# MicroMySens-v003.net
KiCad netlist of a schematic drawn in EAGLE
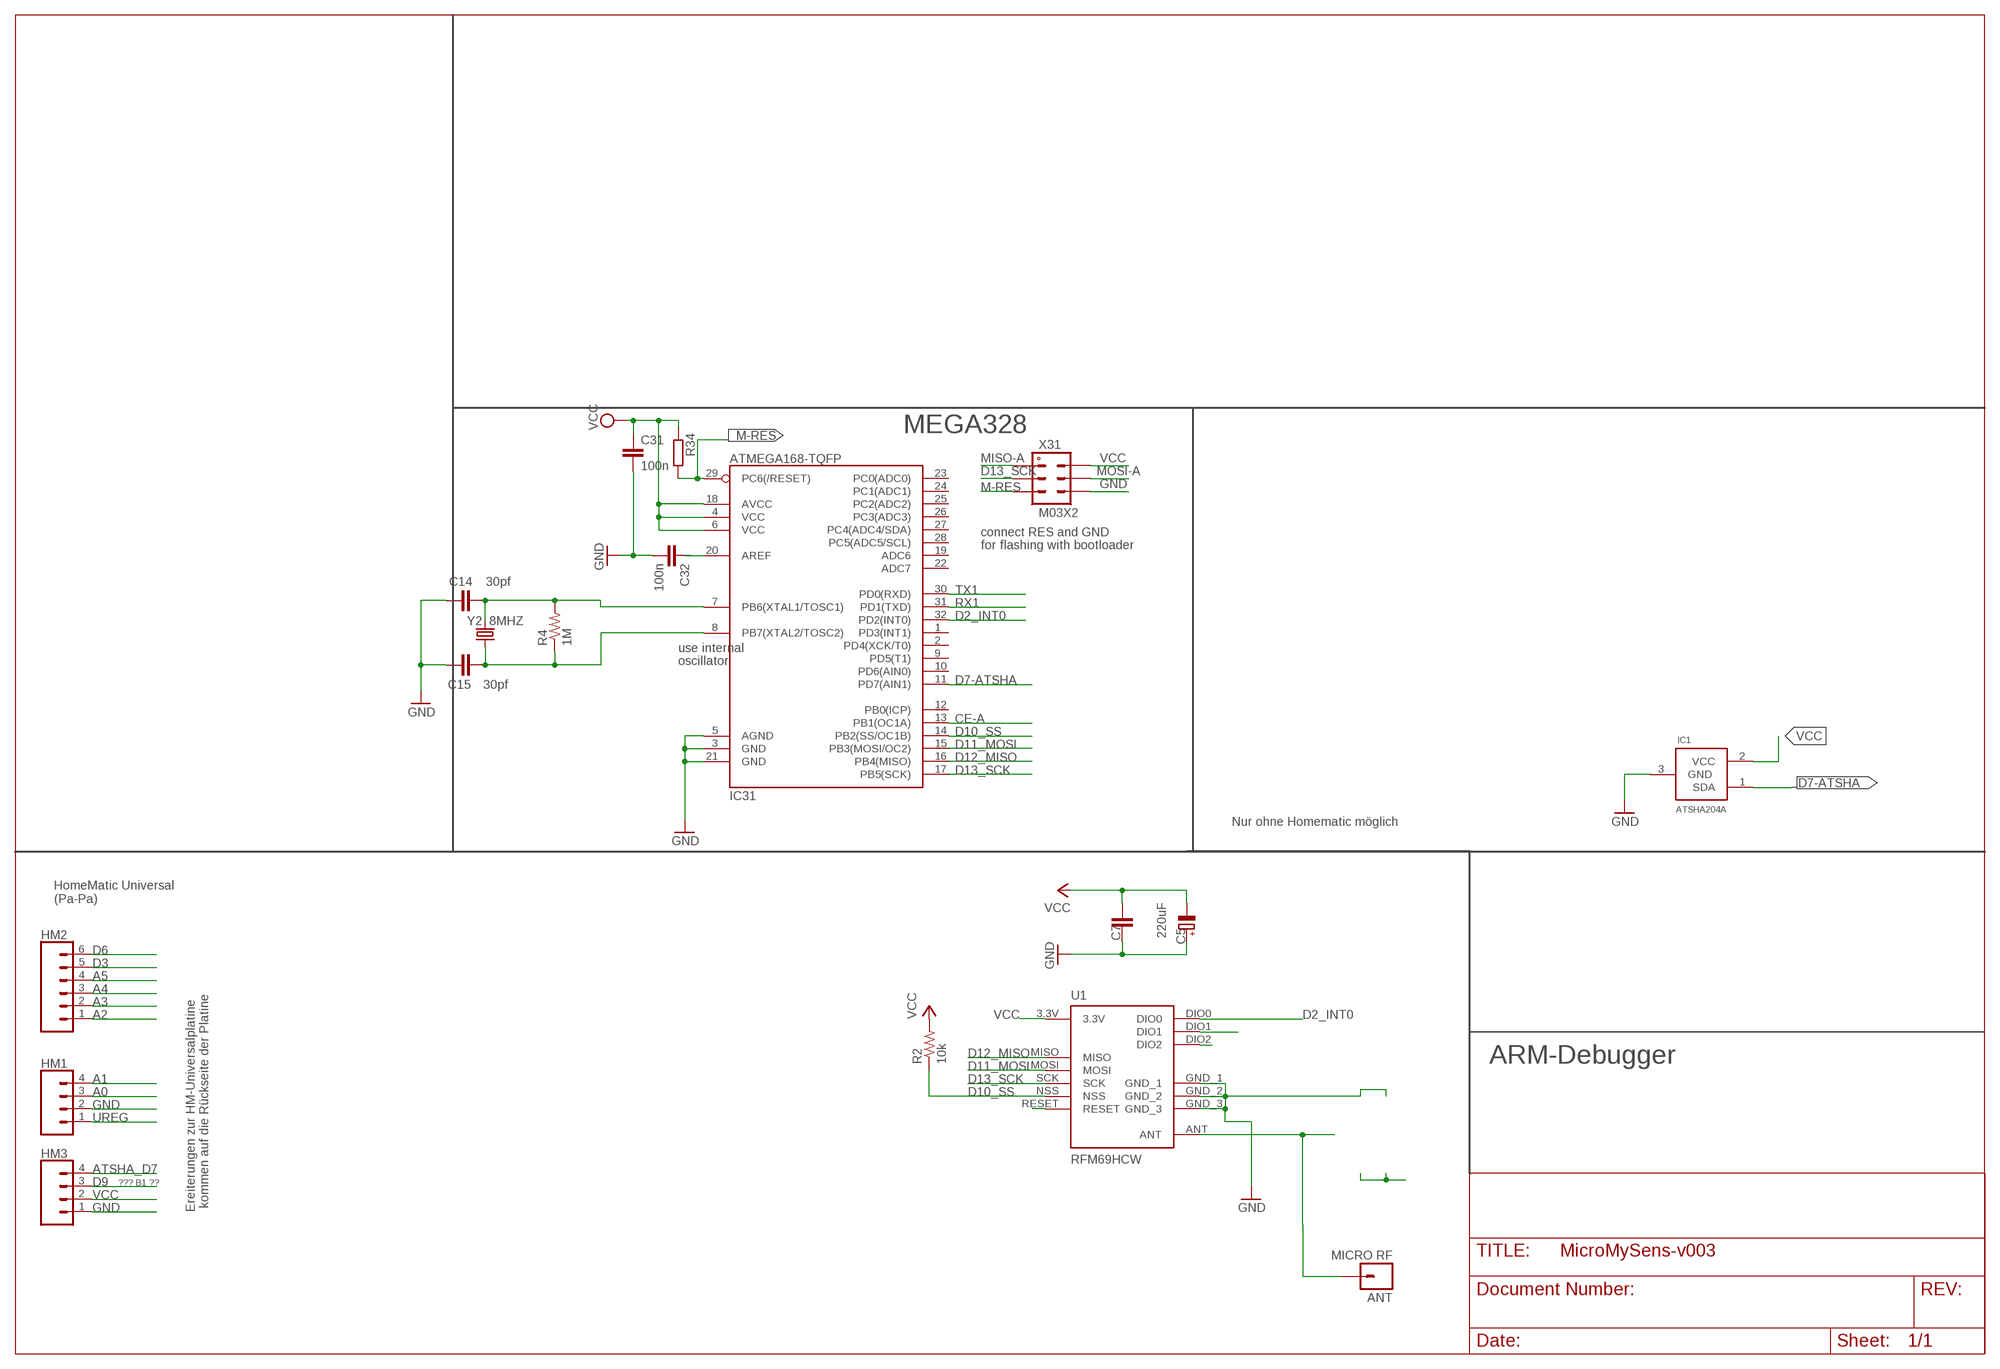
[diagram p0: schematic, sheet 1]

(export (version "E")
  (design (tool "Eeschema 10.0.6"))
  (components
    (comp (ref "ANT")
      (value "MICRO RF")
      (footprint "eagle-import:1X01")
      (libsource (lib "eagle-import") (part "M01PTH"))
    )
    (comp (ref "C5")
      (value "220uF")
      (footprint "eagle-import:E5-8,5")
      (libsource (lib "eagle-import") (part "CPOL-EUE5-8.5"))
    )
    (comp (ref "C7")
      (value "C-EUC1812")
      (footprint "eagle-import:C1812")
      (libsource (lib "eagle-import") (part "C-EUC1812"))
    )
    (comp (ref "C14")
      (value "30pf")
      (footprint "eagle-import:0805")
      (libsource (lib "eagle-import") (part "CAP0805"))
    )
    (comp (ref "C15")
      (value "30pf")
      (footprint "eagle-import:0805")
      (libsource (lib "eagle-import") (part "CAP0805"))
    )
    (comp (ref "C31")
      (value "100n")
      (footprint "eagle-import:C0805")
      (libsource (lib "eagle-import") (part "C-EUC0805"))
    )
    (comp (ref "C32")
      (value "100n")
      (footprint "eagle-import:C0805")
      (libsource (lib "eagle-import") (part "C-EUC0805"))
    )
    (comp (ref "HM1")
      (value "CONN_04")
      (footprint "eagle-import:1X04")
      (libsource (lib "eagle-import") (part "CONN_04"))
    )
    (comp (ref "HM2")
      (value "CONN_06SILK_FEMALE_PTH")
      (footprint "eagle-import:1X06")
      (libsource (lib "eagle-import") (part "CONN_06SILK_FEMALE_PTH"))
    )
    (comp (ref "HM3")
      (value "CONN_04")
      (footprint "eagle-import:1X04")
      (libsource (lib "eagle-import") (part "CONN_04"))
    )
    (comp (ref "IC1")
      (value "ATSHA204A")
      (footprint "eagle-import:SOT23")
      (libsource (lib "eagle-import") (part "ATSHA204A"))
    )
    (comp (ref "IC31")
      (value "ATMEGA168-TQFP")
      (footprint "eagle-import:TQFP32-08")
      (libsource (lib "eagle-import") (part "ATMEGA168-TQFP"))
    )
    (comp (ref "R2")
      (value "10k")
      (footprint "eagle-import:0805")
      (libsource (lib "eagle-import") (part "RESISTOR0805-RES"))
    )
    (comp (ref "R4")
      (value "1M")
      (footprint "eagle-import:0805")
      (libsource (lib "eagle-import") (part "RESISTOR0805-RES"))
    )
    (comp (ref "R34")
      (value "R-EU_R0805")
      (footprint "eagle-import:R0805")
      (libsource (lib "eagle-import") (part "R-EU_R0805"))
    )
    (comp (ref "U1")
      (value "RFM69HCW")
      (footprint "eagle-import:RFM69HCW-XXXS2")
      (libsource (lib "eagle-import") (part "RFM69HCW"))
    )
    (comp (ref "X31")
      (value "M03X2")
      (footprint "eagle-import:2X03-1.27MM_SMD")
      (libsource (lib "eagle-import") (part "M03X2"))
    )
    (comp (ref "Y2")
      (value "8MHZ")
      (footprint "eagle-import:CRYSTAL-TXC-7A")
      (libsource (lib "eagle-import") (part "CRYSTALTXC-7A"))
    )
  )
  (nets
    (net (code "1") (name "/A0") (class "Default")
      (node (ref "HM1") (pin "3") (pinfunction "3_3") (pintype "passive"))
    )
    (net (code "2") (name "/A1") (class "Default")
      (node (ref "HM1") (pin "4") (pinfunction "4_4") (pintype "passive"))
    )
    (net (code "3") (name "/A2") (class "Default")
      (node (ref "HM2") (pin "1") (pinfunction "1_1") (pintype "passive"))
    )
    (net (code "4") (name "/A3") (class "Default")
      (node (ref "HM2") (pin "2") (pinfunction "2_2") (pintype "passive"))
    )
    (net (code "5") (name "/A4") (class "Default")
      (node (ref "HM2") (pin "3") (pinfunction "3_3") (pintype "passive"))
    )
    (net (code "6") (name "/A5") (class "Default")
      (node (ref "HM2") (pin "4") (pinfunction "4_4") (pintype "passive"))
    )
    (net (code "7") (name "/ATSHA_D7") (class "Default")
      (node (ref "HM3") (pin "4") (pinfunction "4_4") (pintype "passive"))
    )
    (net (code "8") (name "/CE-A") (class "Default")
      (node (ref "IC31") (pin "13") (pinfunction "PB1(OC1A)_13") (pintype "bidirectional"))
    )
    (net (code "9") (name "/D2_INT0") (class "Default")
      (node (ref "IC31") (pin "32") (pinfunction "PD2(INT0)_32") (pintype "bidirectional"))
      (node (ref "U1") (pin "DIO0") (pinfunction "DIO0_DIO0") (pintype "bidirectional"))
    )
    (net (code "10") (name "/D3") (class "Default")
      (node (ref "HM2") (pin "5") (pinfunction "5_5") (pintype "passive"))
    )
    (net (code "11") (name "/D6") (class "Default")
      (node (ref "HM2") (pin "6") (pinfunction "6_6") (pintype "passive"))
    )
    (net (code "12") (name "/D7-ATSHA") (class "Default")
      (node (ref "IC1") (pin "1") (pinfunction "SDA_1") (pintype "bidirectional"))
      (node (ref "IC31") (pin "11") (pinfunction "PD7(AIN1)_11") (pintype "bidirectional"))
    )
    (net (code "13") (name "/D9") (class "Default")
      (node (ref "HM3") (pin "3") (pinfunction "3_3") (pintype "passive"))
    )
    (net (code "14") (name "/D10_SS") (class "Default")
      (node (ref "IC31") (pin "14") (pinfunction "PB2(SS/OC1B)_14") (pintype "bidirectional"))
      (node (ref "R2") (pin "1") (pinfunction "1_1") (pintype "passive"))
      (node (ref "U1") (pin "NSS") (pinfunction "NSS_NSS") (pintype "input"))
    )
    (net (code "15") (name "/D11_MOSI") (class "Default")
      (node (ref "IC31") (pin "15") (pinfunction "PB3(MOSI/OC2)_15") (pintype "bidirectional"))
      (node (ref "U1") (pin "MOSI") (pinfunction "MOSI_MOSI") (pintype "input"))
    )
    (net (code "16") (name "/D12_MISO") (class "Default")
      (node (ref "IC31") (pin "16") (pinfunction "PB4(MISO)_16") (pintype "bidirectional"))
      (node (ref "U1") (pin "MISO") (pinfunction "MISO_MISO") (pintype "bidirectional"))
    )
    (net (code "17") (name "/D13_SCK") (class "Default")
      (node (ref "IC31") (pin "17") (pinfunction "PB5(SCK)_17") (pintype "bidirectional"))
      (node (ref "U1") (pin "SCK") (pinfunction "SCK_SCK") (pintype "input"))
      (node (ref "X31") (pin "P$3") (pinfunction "3_P$3") (pintype "passive"))
    )
    (net (code "18") (name "/M-RES") (class "Default")
      (node (ref "IC31") (pin "29") (pinfunction "PC6(/RESET)_29") (pintype "bidirectional"))
      (node (ref "R34") (pin "2") (pinfunction "2_2") (pintype "passive"))
      (node (ref "X31") (pin "P$5") (pinfunction "5_P$5") (pintype "passive"))
    )
    (net (code "19") (name "/MISO-A") (class "Default")
      (node (ref "X31") (pin "P$1") (pinfunction "1_P$1") (pintype "passive"))
    )
    (net (code "20") (name "/MOSI-A") (class "Default")
      (node (ref "X31") (pin "P$4") (pinfunction "4_P$4") (pintype "passive"))
    )
    (net (code "21") (name "/RX1") (class "Default")
      (node (ref "IC31") (pin "31") (pinfunction "PD1(TXD)_31") (pintype "bidirectional"))
    )
    (net (code "22") (name "/TX1") (class "Default")
      (node (ref "IC31") (pin "30") (pinfunction "PD0(RXD)_30") (pintype "bidirectional"))
    )
    (net (code "23") (name "/UREG") (class "Default")
      (node (ref "HM1") (pin "1") (pinfunction "1_1") (pintype "passive"))
    )
    (net (code "24") (name "GND") (class "Default")
      (node (ref "C14") (pin "1") (pinfunction "1_1") (pintype "passive"))
      (node (ref "C15") (pin "1") (pinfunction "1_1") (pintype "passive"))
      (node (ref "C31") (pin "2") (pinfunction "2_2") (pintype "passive"))
      (node (ref "C32") (pin "2") (pinfunction "2_2") (pintype "passive"))
      (node (ref "C5") (pin "+") (pinfunction "+_+") (pintype "passive"))
      (node (ref "C7") (pin "2") (pinfunction "2_2") (pintype "passive"))
      (node (ref "HM1") (pin "2") (pinfunction "2_2") (pintype "passive"))
      (node (ref "HM3") (pin "1") (pinfunction "1_1") (pintype "passive"))
      (node (ref "IC1") (pin "3") (pinfunction "GND_3") (pintype "bidirectional"))
      (node (ref "IC31") (pin "21") (pinfunction "GND_21") (pintype "bidirectional"))
      (node (ref "IC31") (pin "3") (pinfunction "GND_3") (pintype "bidirectional"))
      (node (ref "IC31") (pin "5") (pinfunction "AGND_5") (pintype "bidirectional"))
      (node (ref "U1") (pin "GND_1") (pinfunction "GND_1_GND_1") (pintype "power_in"))
      (node (ref "U1") (pin "GND_2") (pinfunction "GND_2_GND_2") (pintype "power_in"))
      (node (ref "U1") (pin "GND_3") (pinfunction "GND_3_GND_3") (pintype "power_in"))
      (node (ref "X31") (pin "P$6") (pinfunction "6_P$6") (pintype "passive"))
    )
    (net (code "25") (name "Net-(ANT-Pad1)") (class "Default")
      (node (ref "ANT") (pin "1") (pinfunction "1_1") (pintype "passive"))
      (node (ref "U1") (pin "ANT") (pinfunction "ANT_ANT") (pintype "passive"))
    )
    (net (code "26") (name "Net-(IC31-AREF)") (class "Default")
      (node (ref "C32") (pin "1") (pinfunction "1_1") (pintype "passive"))
      (node (ref "IC31") (pin "20") (pinfunction "AREF_20") (pintype "bidirectional"))
    )
    (net (code "27") (name "Net-(IC31-PB6(XTAL1{slash}TOSC1))") (class "Default")
      (node (ref "C14") (pin "2") (pinfunction "2_2") (pintype "passive"))
      (node (ref "IC31") (pin "7") (pinfunction "PB6(XTAL1/TOSC1)_7") (pintype "bidirectional"))
      (node (ref "R4") (pin "2") (pinfunction "2_2") (pintype "passive"))
      (node (ref "Y2") (pin "P$2") (pinfunction "2_P$2") (pintype "passive"))
    )
    (net (code "28") (name "Net-(IC31-PB7(XTAL2{slash}TOSC2))") (class "Default")
      (node (ref "C15") (pin "2") (pinfunction "2_2") (pintype "passive"))
      (node (ref "IC31") (pin "8") (pinfunction "PB7(XTAL2/TOSC2)_8") (pintype "bidirectional"))
      (node (ref "R4") (pin "1") (pinfunction "1_1") (pintype "passive"))
      (node (ref "Y2") (pin "P$1") (pinfunction "1_P$1") (pintype "passive"))
    )
    (net (code "29") (name "VCC") (class "Default")
      (node (ref "C31") (pin "1") (pinfunction "1_1") (pintype "passive"))
      (node (ref "C5") (pin "-") (pinfunction "-_-") (pintype "passive"))
      (node (ref "C7") (pin "1") (pinfunction "1_1") (pintype "passive"))
      (node (ref "HM3") (pin "2") (pinfunction "2_2") (pintype "passive"))
      (node (ref "IC1") (pin "2") (pinfunction "VCC_2") (pintype "bidirectional"))
      (node (ref "IC31") (pin "18") (pinfunction "AVCC_18") (pintype "bidirectional"))
      (node (ref "IC31") (pin "4") (pinfunction "VCC_4") (pintype "bidirectional"))
      (node (ref "IC31") (pin "6") (pinfunction "VCC_6") (pintype "bidirectional"))
      (node (ref "R2") (pin "2") (pinfunction "2_2") (pintype "passive"))
      (node (ref "R34") (pin "1") (pinfunction "1_1") (pintype "passive"))
      (node (ref "U1") (pin "3.3V") (pinfunction "3.3V_3.3V") (pintype "power_in"))
      (node (ref "X31") (pin "P$2") (pinfunction "2_P$2") (pintype "passive"))
    )
    (net (code "30") (name "unconnected-(IC31-ADC6-Pad19)") (class "Default")
      (node (ref "IC31") (pin "19") (pinfunction "ADC6_19") (pintype "bidirectional"))
    )
    (net (code "31") (name "unconnected-(IC31-ADC7-Pad22)") (class "Default")
      (node (ref "IC31") (pin "22") (pinfunction "ADC7_22") (pintype "bidirectional"))
    )
    (net (code "32") (name "unconnected-(IC31-PB0(ICP)-Pad12)") (class "Default")
      (node (ref "IC31") (pin "12") (pinfunction "PB0(ICP)_12") (pintype "bidirectional"))
    )
    (net (code "33") (name "unconnected-(IC31-PC0(ADC0)-Pad23)") (class "Default")
      (node (ref "IC31") (pin "23") (pinfunction "PC0(ADC0)_23") (pintype "bidirectional"))
    )
    (net (code "34") (name "unconnected-(IC31-PC1(ADC1)-Pad24)") (class "Default")
      (node (ref "IC31") (pin "24") (pinfunction "PC1(ADC1)_24") (pintype "bidirectional"))
    )
    (net (code "35") (name "unconnected-(IC31-PC2(ADC2)-Pad25)") (class "Default")
      (node (ref "IC31") (pin "25") (pinfunction "PC2(ADC2)_25") (pintype "bidirectional"))
    )
    (net (code "36") (name "unconnected-(IC31-PC3(ADC3)-Pad26)") (class "Default")
      (node (ref "IC31") (pin "26") (pinfunction "PC3(ADC3)_26") (pintype "bidirectional"))
    )
    (net (code "37") (name "unconnected-(IC31-PC4(ADC4{slash}SDA)-Pad27)") (class "Default")
      (node (ref "IC31") (pin "27") (pinfunction "PC4(ADC4/SDA)_27") (pintype "bidirectional"))
    )
    (net (code "38") (name "unconnected-(IC31-PC5(ADC5{slash}SCL)-Pad28)") (class "Default")
      (node (ref "IC31") (pin "28") (pinfunction "PC5(ADC5/SCL)_28") (pintype "bidirectional"))
    )
    (net (code "39") (name "unconnected-(IC31-PD3(INT1)-Pad1)") (class "Default")
      (node (ref "IC31") (pin "1") (pinfunction "PD3(INT1)_1") (pintype "bidirectional"))
    )
    (net (code "40") (name "unconnected-(IC31-PD4(XCK{slash}T0)-Pad2)") (class "Default")
      (node (ref "IC31") (pin "2") (pinfunction "PD4(XCK/T0)_2") (pintype "bidirectional"))
    )
    (net (code "41") (name "unconnected-(IC31-PD5(T1)-Pad9)") (class "Default")
      (node (ref "IC31") (pin "9") (pinfunction "PD5(T1)_9") (pintype "bidirectional"))
    )
    (net (code "42") (name "unconnected-(IC31-PD6(AIN0)-Pad10)") (class "Default")
      (node (ref "IC31") (pin "10") (pinfunction "PD6(AIN0)_10") (pintype "bidirectional"))
    )
    (net (code "43") (name "unconnected-(U1-PadDIO1)") (class "Default")
      (node (ref "U1") (pin "DIO1") (pinfunction "DIO1_DIO1") (pintype "bidirectional"))
    )
    (net (code "44") (name "unconnected-(U1-PadDIO2)") (class "Default")
      (node (ref "U1") (pin "DIO2") (pinfunction "DIO2_DIO2") (pintype "bidirectional"))
    )
    (net (code "45") (name "unconnected-(U1-PadRESET)") (class "Default")
      (node (ref "U1") (pin "RESET") (pinfunction "RESET_RESET") (pintype "input"))
    )
  )
)
